# 8_bit_Middle_Rev_A.net
KiCad netlist of a schematic drawn in EAGLE
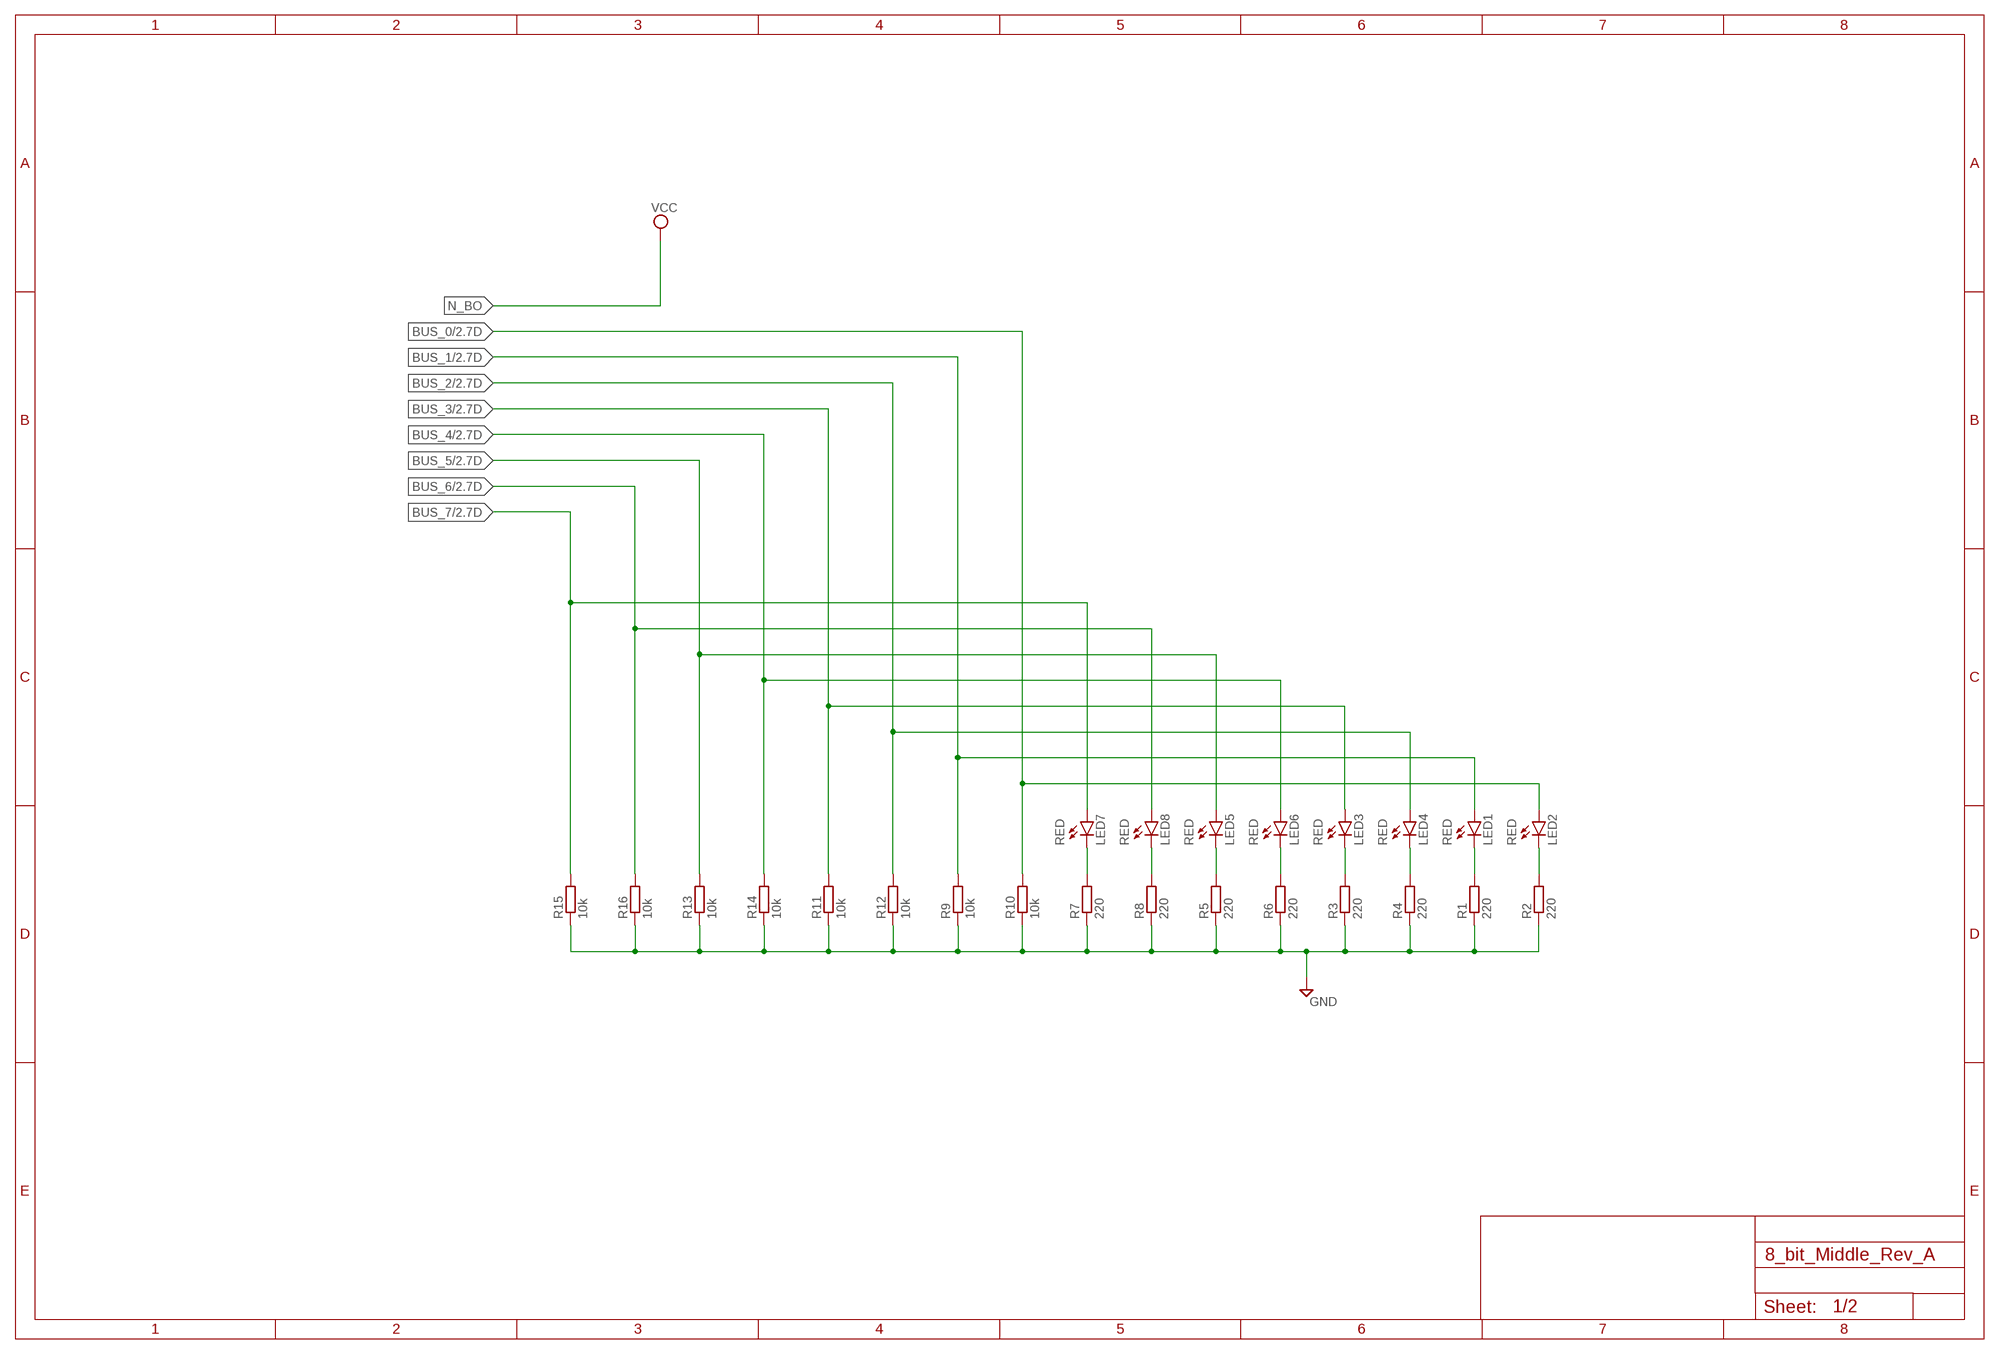
[diagram p0: schematic, sheet 1]
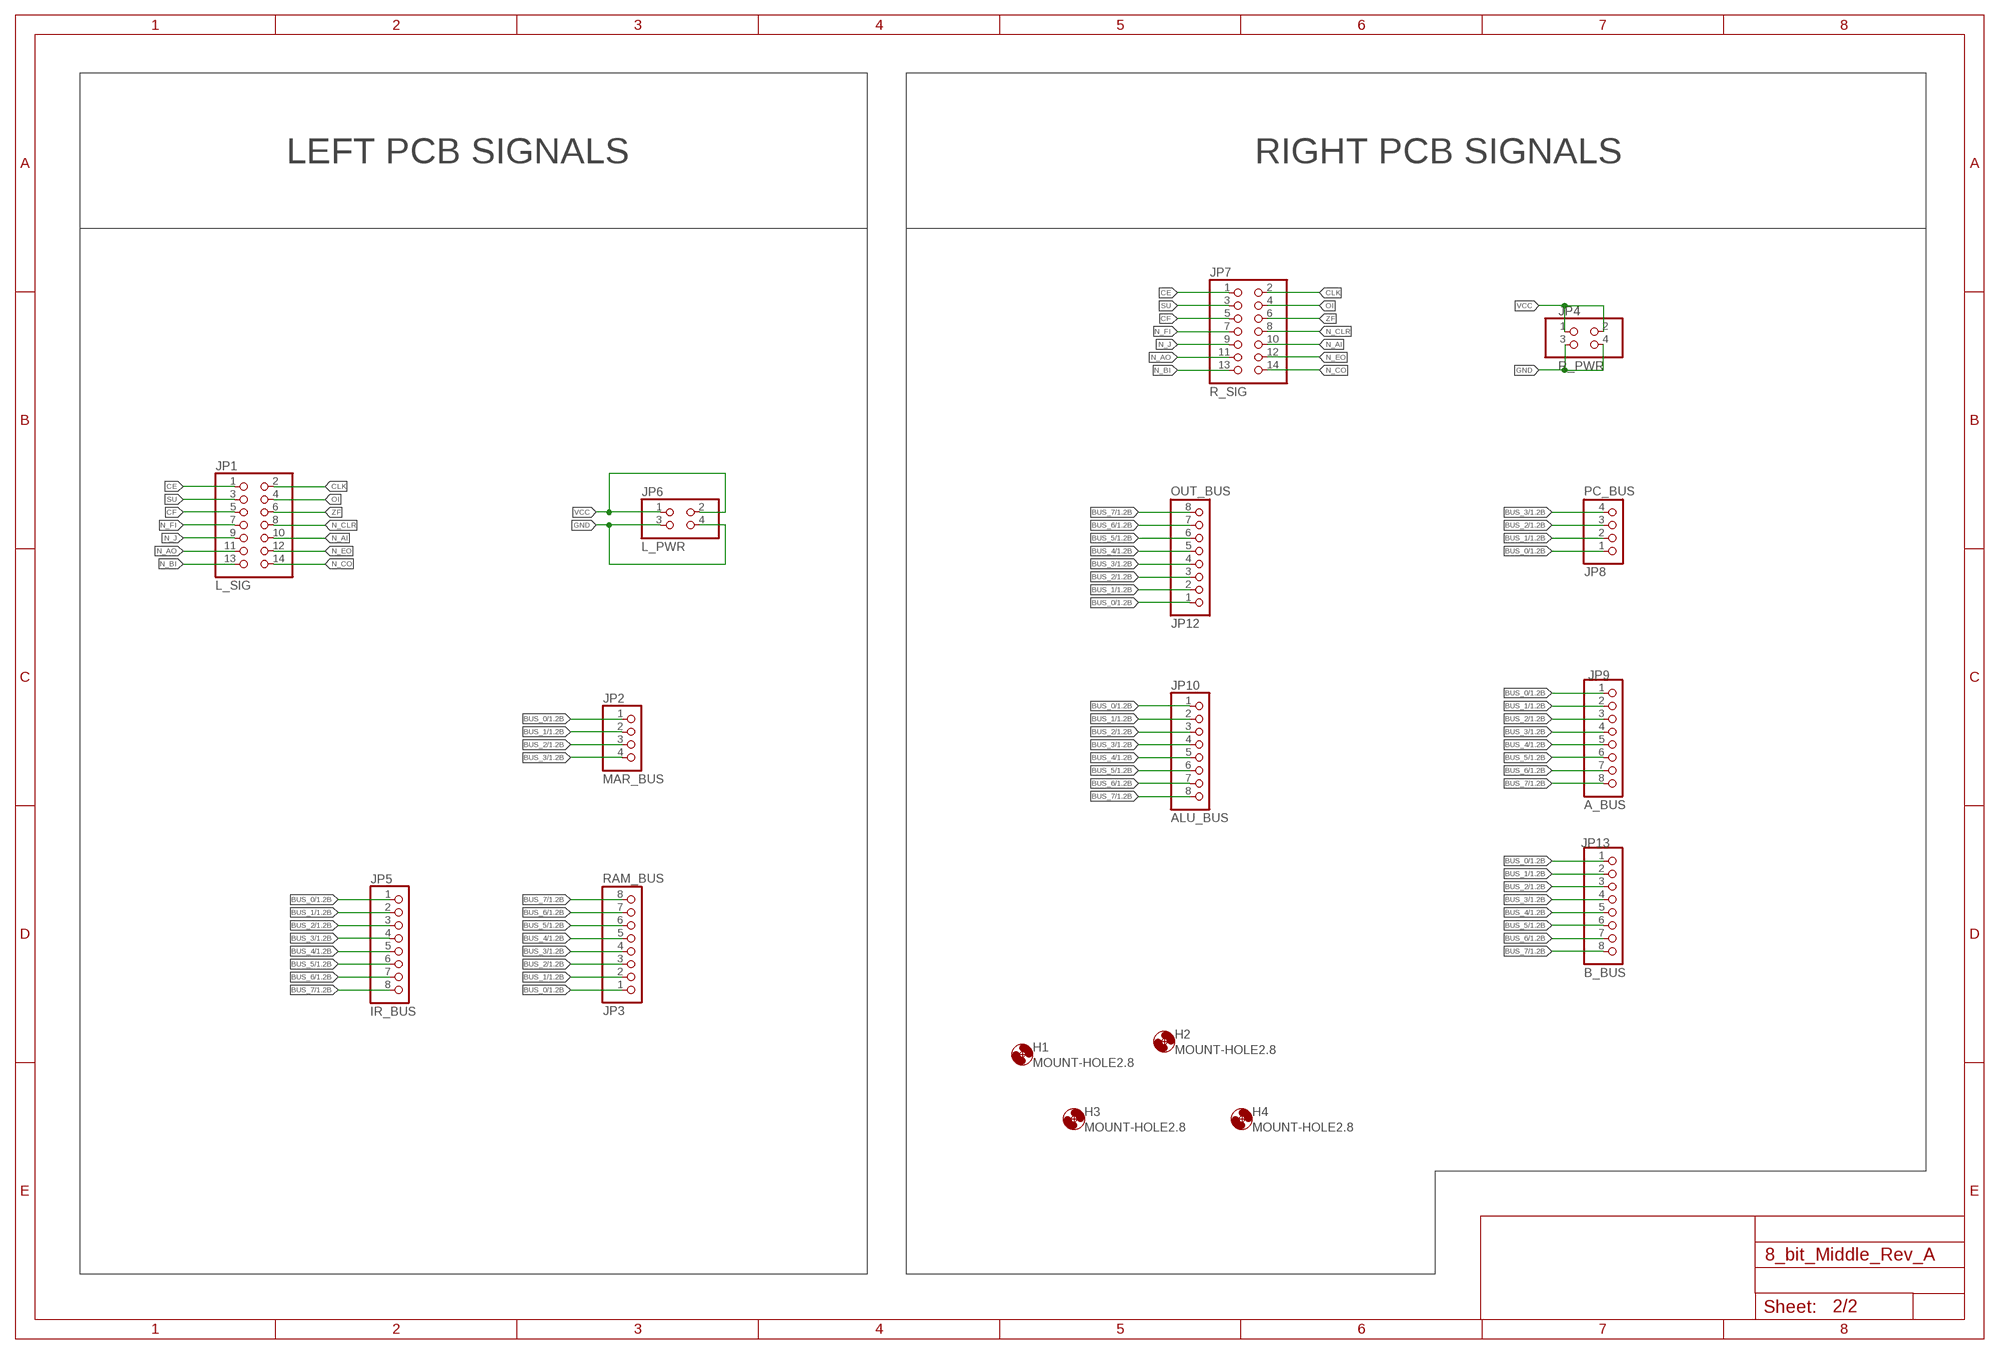
[diagram p1: schematic, sheet 2]

(export (version "E")
  (design (tool "Eeschema 10.0.6"))
  (components
    (comp (ref "H1")
      (value "MOUNT-HOLE2.8")
      (footprint "eagle-import:2,8")
      (libsource (lib "eagle-import") (part "MOUNT-HOLE2.8"))
    )
    (comp (ref "H2")
      (value "MOUNT-HOLE2.8")
      (footprint "eagle-import:2,8")
      (libsource (lib "eagle-import") (part "MOUNT-HOLE2.8"))
    )
    (comp (ref "H3")
      (value "MOUNT-HOLE2.8")
      (footprint "eagle-import:2,8")
      (libsource (lib "eagle-import") (part "MOUNT-HOLE2.8"))
    )
    (comp (ref "H4")
      (value "MOUNT-HOLE2.8")
      (footprint "eagle-import:2,8")
      (libsource (lib "eagle-import") (part "MOUNT-HOLE2.8"))
    )
    (comp (ref "JP1")
      (value "L_SIG")
      (footprint "eagle-import:2X07")
      (libsource (lib "eagle-import") (part "PINHD-2X7"))
    )
    (comp (ref "JP2")
      (value "MAR_BUS")
      (footprint "eagle-import:1X04")
      (libsource (lib "eagle-import") (part "PINHD-1X4"))
    )
    (comp (ref "JP3")
      (value "RAM_BUS")
      (footprint "eagle-import:1X08")
      (libsource (lib "eagle-import") (part "PINHD-1X8"))
    )
    (comp (ref "JP4")
      (value "R_PWR")
      (footprint "eagle-import:2X02")
      (libsource (lib "eagle-import") (part "PINHD-2X2"))
    )
    (comp (ref "JP5")
      (value "IR_BUS")
      (footprint "eagle-import:1X08")
      (libsource (lib "eagle-import") (part "PINHD-1X8"))
    )
    (comp (ref "JP6")
      (value "L_PWR")
      (footprint "eagle-import:2X02")
      (libsource (lib "eagle-import") (part "PINHD-2X2"))
    )
    (comp (ref "JP7")
      (value "R_SIG")
      (footprint "eagle-import:2X07")
      (libsource (lib "eagle-import") (part "PINHD-2X7"))
    )
    (comp (ref "JP8")
      (value "PC_BUS")
      (footprint "eagle-import:1X04")
      (libsource (lib "eagle-import") (part "PINHD-1X4"))
    )
    (comp (ref "JP9")
      (value "A_BUS")
      (footprint "eagle-import:1X08")
      (libsource (lib "eagle-import") (part "PINHD-1X8"))
    )
    (comp (ref "JP10")
      (value "ALU_BUS")
      (footprint "eagle-import:1X08")
      (libsource (lib "eagle-import") (part "PINHD-1X8"))
    )
    (comp (ref "JP12")
      (value "OUT_BUS")
      (footprint "eagle-import:1X08")
      (libsource (lib "eagle-import") (part "PINHD-1X8"))
    )
    (comp (ref "JP13")
      (value "B_BUS")
      (footprint "eagle-import:1X08")
      (libsource (lib "eagle-import") (part "PINHD-1X8"))
    )
    (comp (ref "LED1")
      (value "RED")
      (footprint "eagle-import:LED5MM")
      (libsource (lib "eagle-import") (part "LED5MM"))
    )
    (comp (ref "LED2")
      (value "RED")
      (footprint "eagle-import:LED5MM")
      (libsource (lib "eagle-import") (part "LED5MM"))
    )
    (comp (ref "LED3")
      (value "RED")
      (footprint "eagle-import:LED5MM")
      (libsource (lib "eagle-import") (part "LED5MM"))
    )
    (comp (ref "LED4")
      (value "RED")
      (footprint "eagle-import:LED5MM")
      (libsource (lib "eagle-import") (part "LED5MM"))
    )
    (comp (ref "LED5")
      (value "RED")
      (footprint "eagle-import:LED5MM")
      (libsource (lib "eagle-import") (part "LED5MM"))
    )
    (comp (ref "LED6")
      (value "RED")
      (footprint "eagle-import:LED5MM")
      (libsource (lib "eagle-import") (part "LED5MM"))
    )
    (comp (ref "LED7")
      (value "RED")
      (footprint "eagle-import:LED5MM")
      (libsource (lib "eagle-import") (part "LED5MM"))
    )
    (comp (ref "LED8")
      (value "RED")
      (footprint "eagle-import:LED5MM")
      (libsource (lib "eagle-import") (part "LED5MM"))
    )
    (comp (ref "R1")
      (value "220")
      (footprint "eagle-import:0207_10")
      (libsource (lib "eagle-import") (part "R-EU_0207/10"))
    )
    (comp (ref "R2")
      (value "220")
      (footprint "eagle-import:0207_10")
      (libsource (lib "eagle-import") (part "R-EU_0207/10"))
    )
    (comp (ref "R3")
      (value "220")
      (footprint "eagle-import:0207_10")
      (libsource (lib "eagle-import") (part "R-EU_0207/10"))
    )
    (comp (ref "R4")
      (value "220")
      (footprint "eagle-import:0207_10")
      (libsource (lib "eagle-import") (part "R-EU_0207/10"))
    )
    (comp (ref "R5")
      (value "220")
      (footprint "eagle-import:0207_10")
      (libsource (lib "eagle-import") (part "R-EU_0207/10"))
    )
    (comp (ref "R6")
      (value "220")
      (footprint "eagle-import:0207_10")
      (libsource (lib "eagle-import") (part "R-EU_0207/10"))
    )
    (comp (ref "R7")
      (value "220")
      (footprint "eagle-import:0207_10")
      (libsource (lib "eagle-import") (part "R-EU_0207/10"))
    )
    (comp (ref "R8")
      (value "220")
      (footprint "eagle-import:0207_10")
      (libsource (lib "eagle-import") (part "R-EU_0207/10"))
    )
    (comp (ref "R9")
      (value "10k")
      (footprint "eagle-import:0207_10")
      (libsource (lib "eagle-import") (part "R-EU_0207/10"))
    )
    (comp (ref "R10")
      (value "10k")
      (footprint "eagle-import:0207_10")
      (libsource (lib "eagle-import") (part "R-EU_0207/10"))
    )
    (comp (ref "R11")
      (value "10k")
      (footprint "eagle-import:0207_10")
      (libsource (lib "eagle-import") (part "R-EU_0207/10"))
    )
    (comp (ref "R12")
      (value "10k")
      (footprint "eagle-import:0207_10")
      (libsource (lib "eagle-import") (part "R-EU_0207/10"))
    )
    (comp (ref "R13")
      (value "10k")
      (footprint "eagle-import:0207_10")
      (libsource (lib "eagle-import") (part "R-EU_0207/10"))
    )
    (comp (ref "R14")
      (value "10k")
      (footprint "eagle-import:0207_10")
      (libsource (lib "eagle-import") (part "R-EU_0207/10"))
    )
    (comp (ref "R15")
      (value "10k")
      (footprint "eagle-import:0207_10")
      (libsource (lib "eagle-import") (part "R-EU_0207/10"))
    )
    (comp (ref "R16")
      (value "10k")
      (footprint "eagle-import:0207_10")
      (libsource (lib "eagle-import") (part "R-EU_0207/10"))
    )
  )
  (nets
    (net (code "1") (name "BUS_0") (class "Default")
      (node (ref "JP10") (pin "1") (pinfunction "1_1") (pintype "passive"))
      (node (ref "JP12") (pin "1") (pinfunction "1_1") (pintype "passive"))
      (node (ref "JP13") (pin "1") (pinfunction "1_1") (pintype "passive"))
      (node (ref "JP2") (pin "1") (pinfunction "1_1") (pintype "passive"))
      (node (ref "JP3") (pin "1") (pinfunction "1_1") (pintype "passive"))
      (node (ref "JP5") (pin "1") (pinfunction "1_1") (pintype "passive"))
      (node (ref "JP8") (pin "1") (pinfunction "1_1") (pintype "passive"))
      (node (ref "JP9") (pin "1") (pinfunction "1_1") (pintype "passive"))
      (node (ref "LED2") (pin "A") (pinfunction "A_A") (pintype "passive"))
      (node (ref "R10") (pin "2") (pinfunction "2_2") (pintype "passive"))
    )
    (net (code "2") (name "BUS_1") (class "Default")
      (node (ref "JP10") (pin "2") (pinfunction "2_2") (pintype "passive"))
      (node (ref "JP12") (pin "2") (pinfunction "2_2") (pintype "passive"))
      (node (ref "JP13") (pin "2") (pinfunction "2_2") (pintype "passive"))
      (node (ref "JP2") (pin "2") (pinfunction "2_2") (pintype "passive"))
      (node (ref "JP3") (pin "2") (pinfunction "2_2") (pintype "passive"))
      (node (ref "JP5") (pin "2") (pinfunction "2_2") (pintype "passive"))
      (node (ref "JP8") (pin "2") (pinfunction "2_2") (pintype "passive"))
      (node (ref "JP9") (pin "2") (pinfunction "2_2") (pintype "passive"))
      (node (ref "LED1") (pin "A") (pinfunction "A_A") (pintype "passive"))
      (node (ref "R9") (pin "2") (pinfunction "2_2") (pintype "passive"))
    )
    (net (code "3") (name "BUS_2") (class "Default")
      (node (ref "JP10") (pin "3") (pinfunction "3_3") (pintype "passive"))
      (node (ref "JP12") (pin "3") (pinfunction "3_3") (pintype "passive"))
      (node (ref "JP13") (pin "3") (pinfunction "3_3") (pintype "passive"))
      (node (ref "JP2") (pin "3") (pinfunction "3_3") (pintype "passive"))
      (node (ref "JP3") (pin "3") (pinfunction "3_3") (pintype "passive"))
      (node (ref "JP5") (pin "3") (pinfunction "3_3") (pintype "passive"))
      (node (ref "JP8") (pin "3") (pinfunction "3_3") (pintype "passive"))
      (node (ref "JP9") (pin "3") (pinfunction "3_3") (pintype "passive"))
      (node (ref "LED4") (pin "A") (pinfunction "A_A") (pintype "passive"))
      (node (ref "R12") (pin "2") (pinfunction "2_2") (pintype "passive"))
    )
    (net (code "4") (name "BUS_3") (class "Default")
      (node (ref "JP10") (pin "4") (pinfunction "4_4") (pintype "passive"))
      (node (ref "JP12") (pin "4") (pinfunction "4_4") (pintype "passive"))
      (node (ref "JP13") (pin "4") (pinfunction "4_4") (pintype "passive"))
      (node (ref "JP2") (pin "4") (pinfunction "4_4") (pintype "passive"))
      (node (ref "JP3") (pin "4") (pinfunction "4_4") (pintype "passive"))
      (node (ref "JP5") (pin "4") (pinfunction "4_4") (pintype "passive"))
      (node (ref "JP8") (pin "4") (pinfunction "4_4") (pintype "passive"))
      (node (ref "JP9") (pin "4") (pinfunction "4_4") (pintype "passive"))
      (node (ref "LED3") (pin "A") (pinfunction "A_A") (pintype "passive"))
      (node (ref "R11") (pin "2") (pinfunction "2_2") (pintype "passive"))
    )
    (net (code "5") (name "BUS_4") (class "Default")
      (node (ref "JP10") (pin "5") (pinfunction "5_5") (pintype "passive"))
      (node (ref "JP12") (pin "5") (pinfunction "5_5") (pintype "passive"))
      (node (ref "JP13") (pin "5") (pinfunction "5_5") (pintype "passive"))
      (node (ref "JP3") (pin "5") (pinfunction "5_5") (pintype "passive"))
      (node (ref "JP5") (pin "5") (pinfunction "5_5") (pintype "passive"))
      (node (ref "JP9") (pin "5") (pinfunction "5_5") (pintype "passive"))
      (node (ref "LED6") (pin "A") (pinfunction "A_A") (pintype "passive"))
      (node (ref "R14") (pin "2") (pinfunction "2_2") (pintype "passive"))
    )
    (net (code "6") (name "BUS_5") (class "Default")
      (node (ref "JP10") (pin "6") (pinfunction "6_6") (pintype "passive"))
      (node (ref "JP12") (pin "6") (pinfunction "6_6") (pintype "passive"))
      (node (ref "JP13") (pin "6") (pinfunction "6_6") (pintype "passive"))
      (node (ref "JP3") (pin "6") (pinfunction "6_6") (pintype "passive"))
      (node (ref "JP5") (pin "6") (pinfunction "6_6") (pintype "passive"))
      (node (ref "JP9") (pin "6") (pinfunction "6_6") (pintype "passive"))
      (node (ref "LED5") (pin "A") (pinfunction "A_A") (pintype "passive"))
      (node (ref "R13") (pin "2") (pinfunction "2_2") (pintype "passive"))
    )
    (net (code "7") (name "BUS_6") (class "Default")
      (node (ref "JP10") (pin "7") (pinfunction "7_7") (pintype "passive"))
      (node (ref "JP12") (pin "7") (pinfunction "7_7") (pintype "passive"))
      (node (ref "JP13") (pin "7") (pinfunction "7_7") (pintype "passive"))
      (node (ref "JP3") (pin "7") (pinfunction "7_7") (pintype "passive"))
      (node (ref "JP5") (pin "7") (pinfunction "7_7") (pintype "passive"))
      (node (ref "JP9") (pin "7") (pinfunction "7_7") (pintype "passive"))
      (node (ref "LED8") (pin "A") (pinfunction "A_A") (pintype "passive"))
      (node (ref "R16") (pin "2") (pinfunction "2_2") (pintype "passive"))
    )
    (net (code "8") (name "BUS_7") (class "Default")
      (node (ref "JP10") (pin "8") (pinfunction "8_8") (pintype "passive"))
      (node (ref "JP12") (pin "8") (pinfunction "8_8") (pintype "passive"))
      (node (ref "JP13") (pin "8") (pinfunction "8_8") (pintype "passive"))
      (node (ref "JP3") (pin "8") (pinfunction "8_8") (pintype "passive"))
      (node (ref "JP5") (pin "8") (pinfunction "8_8") (pintype "passive"))
      (node (ref "JP9") (pin "8") (pinfunction "8_8") (pintype "passive"))
      (node (ref "LED7") (pin "A") (pinfunction "A_A") (pintype "passive"))
      (node (ref "R15") (pin "2") (pinfunction "2_2") (pintype "passive"))
    )
    (net (code "9") (name "CE") (class "Default")
      (node (ref "JP1") (pin "1") (pinfunction "1_1") (pintype "passive"))
      (node (ref "JP7") (pin "1") (pinfunction "1_1") (pintype "passive"))
    )
    (net (code "10") (name "CF") (class "Default")
      (node (ref "JP1") (pin "5") (pinfunction "5_5") (pintype "passive"))
      (node (ref "JP7") (pin "5") (pinfunction "5_5") (pintype "passive"))
    )
    (net (code "11") (name "CLK") (class "Default")
      (node (ref "JP1") (pin "2") (pinfunction "2_2") (pintype "passive"))
      (node (ref "JP7") (pin "2") (pinfunction "2_2") (pintype "passive"))
    )
    (net (code "12") (name "GND") (class "Default")
      (node (ref "JP4") (pin "3") (pinfunction "3_3") (pintype "passive"))
      (node (ref "JP4") (pin "4") (pinfunction "4_4") (pintype "passive"))
      (node (ref "JP6") (pin "3") (pinfunction "3_3") (pintype "passive"))
      (node (ref "JP6") (pin "4") (pinfunction "4_4") (pintype "passive"))
      (node (ref "R1") (pin "1") (pinfunction "1_1") (pintype "passive"))
      (node (ref "R10") (pin "1") (pinfunction "1_1") (pintype "passive"))
      (node (ref "R11") (pin "1") (pinfunction "1_1") (pintype "passive"))
      (node (ref "R12") (pin "1") (pinfunction "1_1") (pintype "passive"))
      (node (ref "R13") (pin "1") (pinfunction "1_1") (pintype "passive"))
      (node (ref "R14") (pin "1") (pinfunction "1_1") (pintype "passive"))
      (node (ref "R15") (pin "1") (pinfunction "1_1") (pintype "passive"))
      (node (ref "R16") (pin "1") (pinfunction "1_1") (pintype "passive"))
      (node (ref "R2") (pin "1") (pinfunction "1_1") (pintype "passive"))
      (node (ref "R3") (pin "1") (pinfunction "1_1") (pintype "passive"))
      (node (ref "R4") (pin "1") (pinfunction "1_1") (pintype "passive"))
      (node (ref "R5") (pin "1") (pinfunction "1_1") (pintype "passive"))
      (node (ref "R6") (pin "1") (pinfunction "1_1") (pintype "passive"))
      (node (ref "R7") (pin "1") (pinfunction "1_1") (pintype "passive"))
      (node (ref "R8") (pin "1") (pinfunction "1_1") (pintype "passive"))
      (node (ref "R9") (pin "1") (pinfunction "1_1") (pintype "passive"))
    )
    (net (code "13") (name "N_AI") (class "Default")
      (node (ref "JP1") (pin "10") (pinfunction "10_10") (pintype "passive"))
      (node (ref "JP7") (pin "10") (pinfunction "10_10") (pintype "passive"))
    )
    (net (code "14") (name "N_AO") (class "Default")
      (node (ref "JP1") (pin "11") (pinfunction "11_11") (pintype "passive"))
      (node (ref "JP7") (pin "11") (pinfunction "11_11") (pintype "passive"))
    )
    (net (code "15") (name "N_BI") (class "Default")
      (node (ref "JP1") (pin "13") (pinfunction "13_13") (pintype "passive"))
      (node (ref "JP7") (pin "13") (pinfunction "13_13") (pintype "passive"))
    )
    (net (code "16") (name "N_BO") (class "Default")
      (node (ref "JP4") (pin "1") (pinfunction "1_1") (pintype "passive"))
      (node (ref "JP4") (pin "2") (pinfunction "2_2") (pintype "passive"))
      (node (ref "JP6") (pin "1") (pinfunction "1_1") (pintype "passive"))
      (node (ref "JP6") (pin "2") (pinfunction "2_2") (pintype "passive"))
    )
    (net (code "17") (name "N_CLR") (class "Default")
      (node (ref "JP1") (pin "8") (pinfunction "8_8") (pintype "passive"))
      (node (ref "JP7") (pin "8") (pinfunction "8_8") (pintype "passive"))
    )
    (net (code "18") (name "N_CO") (class "Default")
      (node (ref "JP1") (pin "14") (pinfunction "14_14") (pintype "passive"))
      (node (ref "JP7") (pin "14") (pinfunction "14_14") (pintype "passive"))
    )
    (net (code "19") (name "N_EO") (class "Default")
      (node (ref "JP1") (pin "12") (pinfunction "12_12") (pintype "passive"))
      (node (ref "JP7") (pin "12") (pinfunction "12_12") (pintype "passive"))
    )
    (net (code "20") (name "N_FI") (class "Default")
      (node (ref "JP1") (pin "7") (pinfunction "7_7") (pintype "passive"))
      (node (ref "JP7") (pin "7") (pinfunction "7_7") (pintype "passive"))
    )
    (net (code "21") (name "N_J") (class "Default")
      (node (ref "JP1") (pin "9") (pinfunction "9_9") (pintype "passive"))
      (node (ref "JP7") (pin "9") (pinfunction "9_9") (pintype "passive"))
    )
    (net (code "22") (name "Net-(LED1-C)") (class "Default")
      (node (ref "LED1") (pin "K") (pinfunction "C_K") (pintype "passive"))
      (node (ref "R1") (pin "2") (pinfunction "2_2") (pintype "passive"))
    )
    (net (code "23") (name "Net-(LED2-C)") (class "Default")
      (node (ref "LED2") (pin "K") (pinfunction "C_K") (pintype "passive"))
      (node (ref "R2") (pin "2") (pinfunction "2_2") (pintype "passive"))
    )
    (net (code "24") (name "Net-(LED3-C)") (class "Default")
      (node (ref "LED3") (pin "K") (pinfunction "C_K") (pintype "passive"))
      (node (ref "R3") (pin "2") (pinfunction "2_2") (pintype "passive"))
    )
    (net (code "25") (name "Net-(LED4-C)") (class "Default")
      (node (ref "LED4") (pin "K") (pinfunction "C_K") (pintype "passive"))
      (node (ref "R4") (pin "2") (pinfunction "2_2") (pintype "passive"))
    )
    (net (code "26") (name "Net-(LED5-C)") (class "Default")
      (node (ref "LED5") (pin "K") (pinfunction "C_K") (pintype "passive"))
      (node (ref "R5") (pin "2") (pinfunction "2_2") (pintype "passive"))
    )
    (net (code "27") (name "Net-(LED6-C)") (class "Default")
      (node (ref "LED6") (pin "K") (pinfunction "C_K") (pintype "passive"))
      (node (ref "R6") (pin "2") (pinfunction "2_2") (pintype "passive"))
    )
    (net (code "28") (name "Net-(LED7-C)") (class "Default")
      (node (ref "LED7") (pin "K") (pinfunction "C_K") (pintype "passive"))
      (node (ref "R7") (pin "2") (pinfunction "2_2") (pintype "passive"))
    )
    (net (code "29") (name "Net-(LED8-C)") (class "Default")
      (node (ref "LED8") (pin "K") (pinfunction "C_K") (pintype "passive"))
      (node (ref "R8") (pin "2") (pinfunction "2_2") (pintype "passive"))
    )
    (net (code "30") (name "OI") (class "Default")
      (node (ref "JP1") (pin "4") (pinfunction "4_4") (pintype "passive"))
      (node (ref "JP7") (pin "4") (pinfunction "4_4") (pintype "passive"))
    )
    (net (code "31") (name "SU") (class "Default")
      (node (ref "JP1") (pin "3") (pinfunction "3_3") (pintype "passive"))
      (node (ref "JP7") (pin "3") (pinfunction "3_3") (pintype "passive"))
    )
    (net (code "32") (name "ZF") (class "Default")
      (node (ref "JP1") (pin "6") (pinfunction "6_6") (pintype "passive"))
      (node (ref "JP7") (pin "6") (pinfunction "6_6") (pintype "passive"))
    )
  )
)
